# Board2.net
KiCad netlist of a schematic drawn in EAGLE
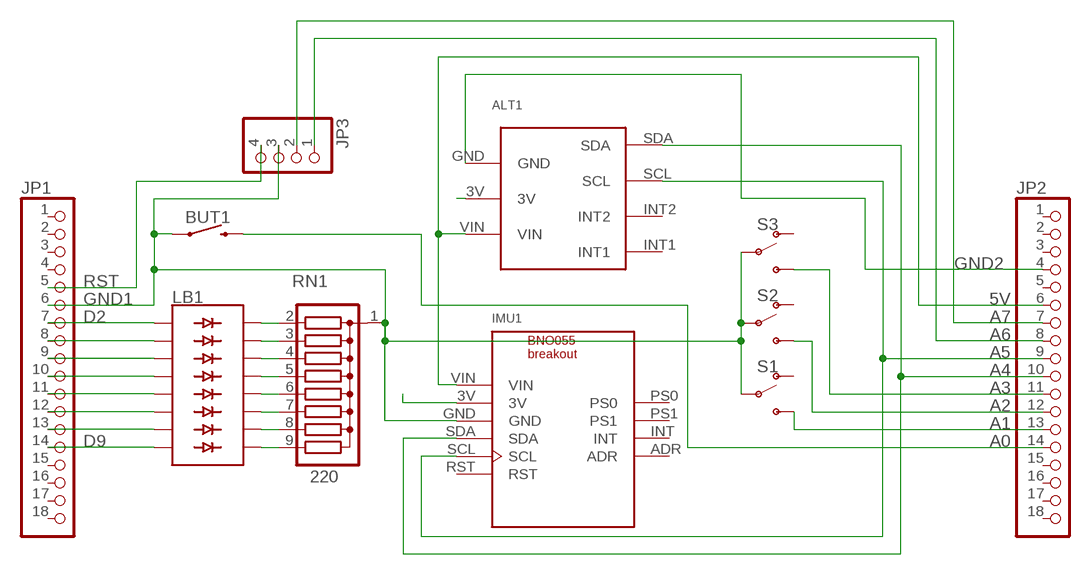
[diagram p0: schematic, sheet 1]

(export (version "E")
  (design (tool "Eeschema 10.0.6"))
  (components
    (comp (ref "ALT1")
      (value "ADA1893")
      (footprint "eagle-import:ADA1893")
      (libsource (lib "eagle-import") (part "ADA1893"))
    )
    (comp (ref "BUT1")
      (value "MOMENTARY-SWITCH-SPST-PTH-6.0MM")
      (footprint "eagle-import:TACTILE_SWITCH_PTH_6.0MM")
      (libsource (lib "eagle-import") (part "MOMENTARY-SWITCH-SPST-PTH-6.0MM"))
    )
    (comp (ref "IMU1")
      (value "ADA2472")
      (footprint "eagle-import:ADA2472")
      (libsource (lib "eagle-import") (part "ADA2472"))
    )
    (comp (ref "JP1")
      (value "PINHD-1X18")
      (footprint "eagle-import:1X18")
      (libsource (lib "eagle-import") (part "PINHD-1X18"))
    )
    (comp (ref "JP2")
      (value "PINHD-1X18")
      (footprint "eagle-import:1X18")
      (libsource (lib "eagle-import") (part "PINHD-1X18"))
    )
    (comp (ref "JP3")
      (value "PINHD-1X4")
      (footprint "eagle-import:1X04")
      (libsource (lib "eagle-import") (part "PINHD-1X4"))
    )
    (comp (ref "LB1")
      (value "LB8")
      (footprint "eagle-import:LB8")
      (libsource (lib "eagle-import") (part "LB8"))
    )
    (comp (ref "RN1")
      (value "220")
      (footprint "eagle-import:SIL9")
      (libsource (lib "eagle-import") (part "G08R"))
    )
    (comp (ref "S1")
      (value "SWITCH-SPDT-PTH-11.6X4.0MM")
      (footprint "eagle-import:SWITCH_SPDT_PTH_11.6X4.0MM")
      (libsource (lib "eagle-import") (part "SWITCH-SPDT-PTH-11.6X4.0MM"))
    )
    (comp (ref "S2")
      (value "SWITCH-SPDT-PTH-11.6X4.0MM")
      (footprint "eagle-import:SWITCH_SPDT_PTH_11.6X4.0MM")
      (libsource (lib "eagle-import") (part "SWITCH-SPDT-PTH-11.6X4.0MM"))
    )
    (comp (ref "S3")
      (value "SWITCH-SPDT-PTH-11.6X4.0MM")
      (footprint "eagle-import:SWITCH_SPDT_PTH_11.6X4.0MM")
      (libsource (lib "eagle-import") (part "SWITCH-SPDT-PTH-11.6X4.0MM"))
    )
  )
  (nets
    (net (code "1") (name "/5V") (class "Default")
      (node (ref "ALT1") (pin "VIN") (pinfunction "VIN_VIN") (pintype "power_in"))
      (node (ref "IMU1") (pin "VIN") (pinfunction "VIN_VIN") (pintype "power_in"))
      (node (ref "JP2") (pin "6") (pinfunction "6_6") (pintype "passive"))
    )
    (net (code "2") (name "/A0") (class "Default")
      (node (ref "BUT1") (pin "3") (pinfunction "2_3") (pintype "passive"))
      (node (ref "JP2") (pin "14") (pinfunction "14_14") (pintype "passive"))
    )
    (net (code "3") (name "/A1") (class "Default")
      (node (ref "JP2") (pin "13") (pinfunction "13_13") (pintype "passive"))
      (node (ref "S1") (pin "3") (pinfunction "S_3") (pintype "passive"))
    )
    (net (code "4") (name "/A2") (class "Default")
      (node (ref "JP2") (pin "12") (pinfunction "12_12") (pintype "passive"))
      (node (ref "S2") (pin "3") (pinfunction "S_3") (pintype "passive"))
    )
    (net (code "5") (name "/A3") (class "Default")
      (node (ref "JP2") (pin "11") (pinfunction "11_11") (pintype "passive"))
      (node (ref "S3") (pin "3") (pinfunction "S_3") (pintype "passive"))
    )
    (net (code "6") (name "/A4") (class "Default")
      (node (ref "ALT1") (pin "SDA") (pinfunction "SDA_SDA") (pintype "bidirectional"))
      (node (ref "IMU1") (pin "SDA") (pinfunction "SDA_SDA") (pintype "bidirectional"))
      (node (ref "JP2") (pin "10") (pinfunction "10_10") (pintype "passive"))
    )
    (net (code "7") (name "/A5") (class "Default")
      (node (ref "ALT1") (pin "SCL") (pinfunction "SCL_SCL") (pintype "input"))
      (node (ref "IMU1") (pin "SCL") (pinfunction "SCL_SCL") (pintype "input"))
      (node (ref "JP2") (pin "9") (pinfunction "9_9") (pintype "passive"))
    )
    (net (code "8") (name "/A6") (class "Default")
      (node (ref "JP2") (pin "8") (pinfunction "8_8") (pintype "passive"))
      (node (ref "JP3") (pin "1") (pinfunction "1_1") (pintype "passive"))
    )
    (net (code "9") (name "/A7") (class "Default")
      (node (ref "JP2") (pin "7") (pinfunction "7_7") (pintype "passive"))
      (node (ref "JP3") (pin "2") (pinfunction "2_2") (pintype "passive"))
    )
    (net (code "10") (name "/D2") (class "Default")
      (node (ref "JP1") (pin "7") (pinfunction "7_7") (pintype "passive"))
      (node (ref "LB1") (pin "1") (pinfunction "A0_1") (pintype "passive"))
    )
    (net (code "11") (name "/D9") (class "Default")
      (node (ref "JP1") (pin "14") (pinfunction "14_14") (pintype "passive"))
      (node (ref "LB1") (pin "8") (pinfunction "A7_8") (pintype "passive"))
    )
    (net (code "12") (name "/GND1") (class "Default")
      (node (ref "BUT1") (pin "1") (pinfunction "1_1") (pintype "passive"))
      (node (ref "IMU1") (pin "GND") (pinfunction "GND_GND") (pintype "power_in"))
      (node (ref "JP1") (pin "6") (pinfunction "6_6") (pintype "passive"))
      (node (ref "JP3") (pin "3") (pinfunction "3_3") (pintype "passive"))
      (node (ref "RN1") (pin "1") (pinfunction "1_1") (pintype "passive"))
      (node (ref "S1") (pin "2") (pinfunction "P_2") (pintype "passive"))
      (node (ref "S2") (pin "2") (pinfunction "P_2") (pintype "passive"))
      (node (ref "S3") (pin "2") (pinfunction "P_2") (pintype "passive"))
    )
    (net (code "13") (name "/GND2") (class "Default")
      (node (ref "ALT1") (pin "GND") (pinfunction "GND_GND") (pintype "power_in"))
      (node (ref "JP2") (pin "4") (pinfunction "4_4") (pintype "passive"))
    )
    (net (code "14") (name "/RST") (class "Default")
      (node (ref "JP1") (pin "5") (pinfunction "5_5") (pintype "passive"))
      (node (ref "JP3") (pin "4") (pinfunction "4_4") (pintype "passive"))
    )
    (net (code "15") (name "Net-(LB1-A1)") (class "Default")
      (node (ref "JP1") (pin "8") (pinfunction "8_8") (pintype "passive"))
      (node (ref "LB1") (pin "2") (pinfunction "A1_2") (pintype "passive"))
    )
    (net (code "16") (name "Net-(LB1-A2)") (class "Default")
      (node (ref "JP1") (pin "9") (pinfunction "9_9") (pintype "passive"))
      (node (ref "LB1") (pin "3") (pinfunction "A2_3") (pintype "passive"))
    )
    (net (code "17") (name "Net-(LB1-A3)") (class "Default")
      (node (ref "JP1") (pin "10") (pinfunction "10_10") (pintype "passive"))
      (node (ref "LB1") (pin "4") (pinfunction "A3_4") (pintype "passive"))
    )
    (net (code "18") (name "Net-(LB1-A4)") (class "Default")
      (node (ref "JP1") (pin "11") (pinfunction "11_11") (pintype "passive"))
      (node (ref "LB1") (pin "5") (pinfunction "A4_5") (pintype "passive"))
    )
    (net (code "19") (name "Net-(LB1-A5)") (class "Default")
      (node (ref "JP1") (pin "12") (pinfunction "12_12") (pintype "passive"))
      (node (ref "LB1") (pin "6") (pinfunction "A5_6") (pintype "passive"))
    )
    (net (code "20") (name "Net-(LB1-A6)") (class "Default")
      (node (ref "JP1") (pin "13") (pinfunction "13_13") (pintype "passive"))
      (node (ref "LB1") (pin "7") (pinfunction "A6_7") (pintype "passive"))
    )
    (net (code "21") (name "Net-(LB1-C0)") (class "Default")
      (node (ref "LB1") (pin "16") (pinfunction "C0_16") (pintype "passive"))
      (node (ref "RN1") (pin "2") (pinfunction "2_2") (pintype "passive"))
    )
    (net (code "22") (name "Net-(LB1-C1)") (class "Default")
      (node (ref "LB1") (pin "15") (pinfunction "C1_15") (pintype "passive"))
      (node (ref "RN1") (pin "3") (pinfunction "3_3") (pintype "passive"))
    )
    (net (code "23") (name "Net-(LB1-C2)") (class "Default")
      (node (ref "LB1") (pin "14") (pinfunction "C2_14") (pintype "passive"))
      (node (ref "RN1") (pin "4") (pinfunction "4_4") (pintype "passive"))
    )
    (net (code "24") (name "Net-(LB1-C3)") (class "Default")
      (node (ref "LB1") (pin "13") (pinfunction "C3_13") (pintype "passive"))
      (node (ref "RN1") (pin "5") (pinfunction "5_5") (pintype "passive"))
    )
    (net (code "25") (name "Net-(LB1-C4)") (class "Default")
      (node (ref "LB1") (pin "12") (pinfunction "C4_12") (pintype "passive"))
      (node (ref "RN1") (pin "6") (pinfunction "6_6") (pintype "passive"))
    )
    (net (code "26") (name "Net-(LB1-C5)") (class "Default")
      (node (ref "LB1") (pin "11") (pinfunction "C5_11") (pintype "passive"))
      (node (ref "RN1") (pin "7") (pinfunction "7_7") (pintype "passive"))
    )
    (net (code "27") (name "Net-(LB1-C6)") (class "Default")
      (node (ref "LB1") (pin "10") (pinfunction "C6_10") (pintype "passive"))
      (node (ref "RN1") (pin "8") (pinfunction "8_8") (pintype "passive"))
    )
    (net (code "28") (name "Net-(LB1-C7)") (class "Default")
      (node (ref "LB1") (pin "9") (pinfunction "C7_9") (pintype "passive"))
      (node (ref "RN1") (pin "9") (pinfunction "9_9") (pintype "passive"))
    )
    (net (code "29") (name "unconnected-(ALT1-Pad3V)") (class "Default")
      (node (ref "ALT1") (pin "3V") (pinfunction "3V_3V") (pintype "power_in"))
    )
    (net (code "30") (name "unconnected-(ALT1-PadINT1)") (class "Default")
      (node (ref "ALT1") (pin "INT1") (pinfunction "INT1_INT1") (pintype "output"))
    )
    (net (code "31") (name "unconnected-(ALT1-PadINT2)") (class "Default")
      (node (ref "ALT1") (pin "INT2") (pinfunction "INT2_INT2") (pintype "output"))
    )
    (net (code "32") (name "unconnected-(IMU1-Pad3V)") (class "Default")
      (node (ref "IMU1") (pin "3V") (pinfunction "3V_3V") (pintype "power_in"))
    )
    (net (code "33") (name "unconnected-(IMU1-PadADR)") (class "Default")
      (node (ref "IMU1") (pin "ADR") (pinfunction "ADR_ADR") (pintype "input"))
    )
    (net (code "34") (name "unconnected-(IMU1-PadINT)") (class "Default")
      (node (ref "IMU1") (pin "INT") (pinfunction "INT_INT") (pintype "output"))
    )
    (net (code "35") (name "unconnected-(IMU1-PadPS0)") (class "Default")
      (node (ref "IMU1") (pin "PS0") (pinfunction "PS0_PS0") (pintype "input"))
    )
    (net (code "36") (name "unconnected-(IMU1-PadPS1)") (class "Default")
      (node (ref "IMU1") (pin "PS1") (pinfunction "PS1_PS1") (pintype "input"))
    )
    (net (code "37") (name "unconnected-(IMU1-PadRST)") (class "Default")
      (node (ref "IMU1") (pin "RST") (pinfunction "RST_RST") (pintype "input"))
    )
    (net (code "38") (name "unconnected-(JP1-Pad1)") (class "Default")
      (node (ref "JP1") (pin "1") (pinfunction "1_1") (pintype "passive"))
    )
    (net (code "39") (name "unconnected-(JP1-Pad2)") (class "Default")
      (node (ref "JP1") (pin "2") (pinfunction "2_2") (pintype "passive"))
    )
    (net (code "40") (name "unconnected-(JP1-Pad3)") (class "Default")
      (node (ref "JP1") (pin "3") (pinfunction "3_3") (pintype "passive"))
    )
    (net (code "41") (name "unconnected-(JP1-Pad4)") (class "Default")
      (node (ref "JP1") (pin "4") (pinfunction "4_4") (pintype "passive"))
    )
    (net (code "42") (name "unconnected-(JP1-Pad15)") (class "Default")
      (node (ref "JP1") (pin "15") (pinfunction "15_15") (pintype "passive"))
    )
    (net (code "43") (name "unconnected-(JP1-Pad16)") (class "Default")
      (node (ref "JP1") (pin "16") (pinfunction "16_16") (pintype "passive"))
    )
    (net (code "44") (name "unconnected-(JP1-Pad17)") (class "Default")
      (node (ref "JP1") (pin "17") (pinfunction "17_17") (pintype "passive"))
    )
    (net (code "45") (name "unconnected-(JP1-Pad18)") (class "Default")
      (node (ref "JP1") (pin "18") (pinfunction "18_18") (pintype "passive"))
    )
    (net (code "46") (name "unconnected-(JP2-Pad1)") (class "Default")
      (node (ref "JP2") (pin "1") (pinfunction "1_1") (pintype "passive"))
    )
    (net (code "47") (name "unconnected-(JP2-Pad2)") (class "Default")
      (node (ref "JP2") (pin "2") (pinfunction "2_2") (pintype "passive"))
    )
    (net (code "48") (name "unconnected-(JP2-Pad3)") (class "Default")
      (node (ref "JP2") (pin "3") (pinfunction "3_3") (pintype "passive"))
    )
    (net (code "49") (name "unconnected-(JP2-Pad5)") (class "Default")
      (node (ref "JP2") (pin "5") (pinfunction "5_5") (pintype "passive"))
    )
    (net (code "50") (name "unconnected-(JP2-Pad15)") (class "Default")
      (node (ref "JP2") (pin "15") (pinfunction "15_15") (pintype "passive"))
    )
    (net (code "51") (name "unconnected-(JP2-Pad16)") (class "Default")
      (node (ref "JP2") (pin "16") (pinfunction "16_16") (pintype "passive"))
    )
    (net (code "52") (name "unconnected-(JP2-Pad17)") (class "Default")
      (node (ref "JP2") (pin "17") (pinfunction "17_17") (pintype "passive"))
    )
    (net (code "53") (name "unconnected-(JP2-Pad18)") (class "Default")
      (node (ref "JP2") (pin "18") (pinfunction "18_18") (pintype "passive"))
    )
    (net (code "54") (name "unconnected-(S1-O-Pad1)") (class "Default")
      (node (ref "S1") (pin "1") (pinfunction "O_1") (pintype "passive"))
    )
    (net (code "55") (name "unconnected-(S2-O-Pad1)") (class "Default")
      (node (ref "S2") (pin "1") (pinfunction "O_1") (pintype "passive"))
    )
    (net (code "56") (name "unconnected-(S3-O-Pad1)") (class "Default")
      (node (ref "S3") (pin "1") (pinfunction "O_1") (pintype "passive"))
    )
  )
)
